# Wifi.net
KiCad netlist of a schematic drawn in Altium Designer
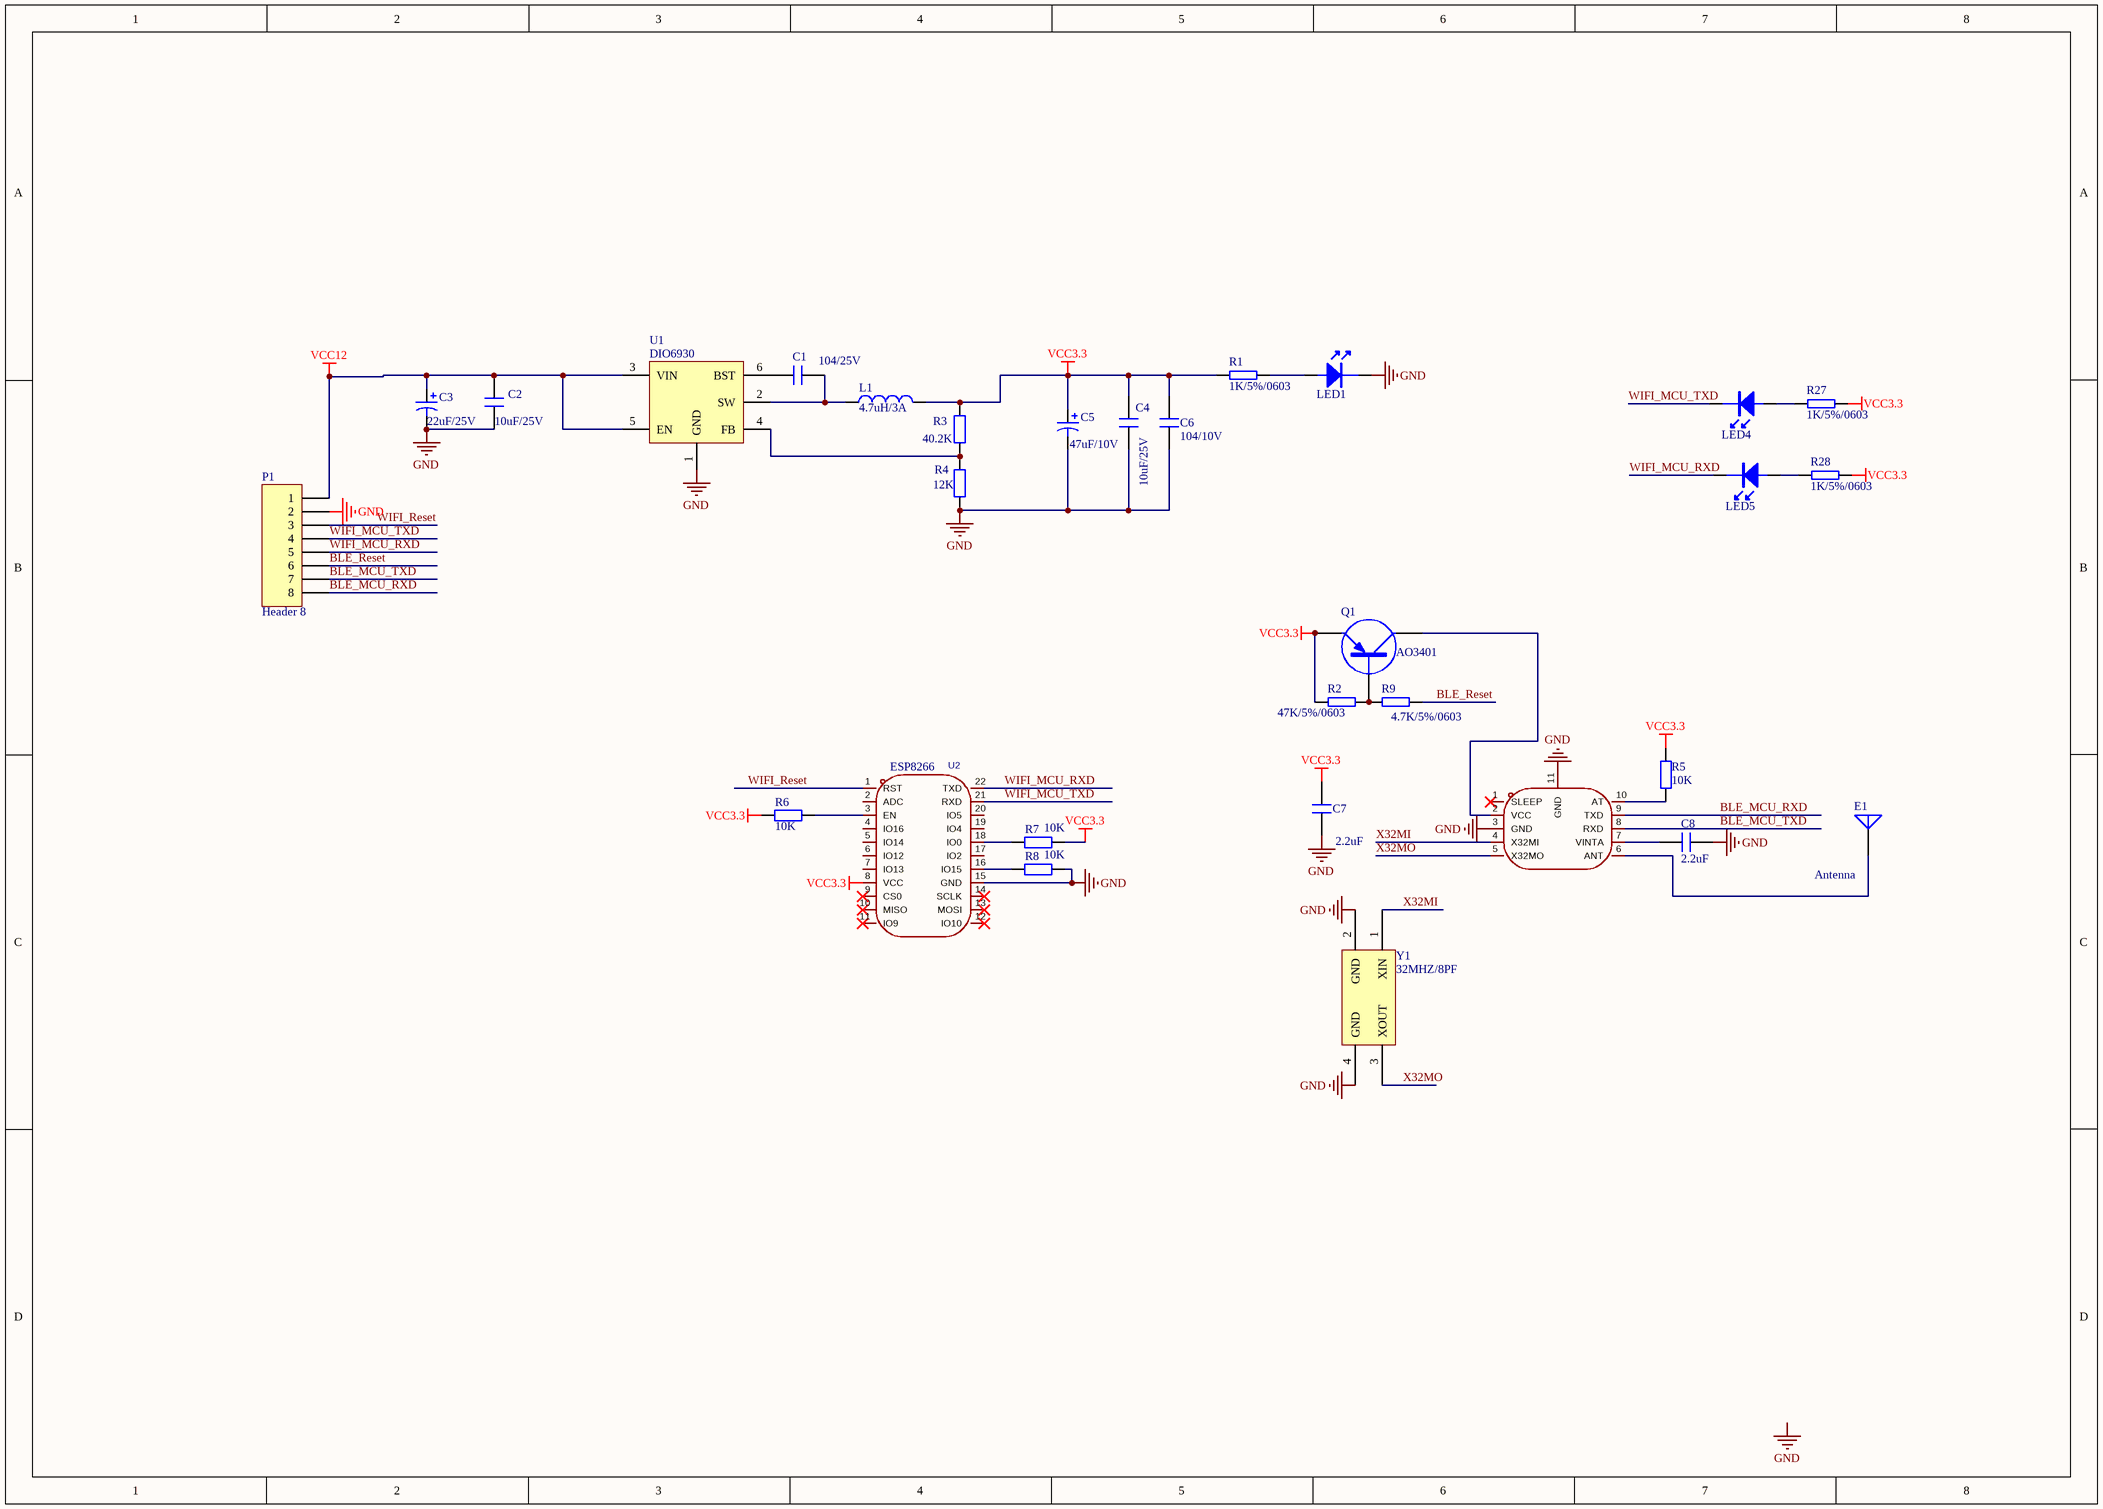
[diagram p0: Wifi.SchDoc]

(export (version "E")
  (design (tool "Eeschema 10.0.6"))
  (components
    (comp (ref "C1") (value "104/25V") (footprint "0603R") (libsource (lib "ES_Schematic") (part "CAP_1")))
    (comp (ref "C2") (value "10uF/25V") (footprint "0603R") (libsource (lib "ES_Schematic") (part "CAP")))
    (comp (ref "C3")
      (value "22uF/25V")
      (footprint "0805R")
      (description "Polarized Capacitor (Radial)")
      (fields (field (name "PUBLISHER") "Altium Limited"))
      (libsource (lib "Miscellaneous Devices") (part "Cap Pol1"))
    )
    (comp (ref "C4") (value "10uF/25V") (footprint "0603R") (libsource (lib "ES_Schematic") (part "CAP")))
    (comp (ref "C5")
      (value "47uF/10V")
      (footprint "0805R")
      (description "Polarized Capacitor (Radial)")
      (fields (field (name "PUBLISHER") "Altium Limited"))
      (libsource (lib "Miscellaneous Devices") (part "Cap Pol1"))
    )
    (comp (ref "C6") (value "104/10V") (footprint "0603R") (libsource (lib "ES_Schematic") (part "CAP_1")))
    (comp (ref "C7") (value "2.2uF") (footprint "0603R") (libsource (lib "ES_Schematic") (part "CAP_1")))
    (comp (ref "C8") (value "2.2uF") (footprint "0603R") (libsource (lib "ES_Schematic") (part "CAP_1")))
    (comp (ref "E1")
      (value "Antenna")
      (footprint "ANT-F-1-2.4G-1.6mmFR4-WCH")
      (description "Generic Antenna")
      (fields (field (name "PUBLISHER") "Altium Limited"))
      (libsource (lib "Miscellaneous Devices") (part "Antenna"))
    )
    (comp (ref "L1")
      (value "4.7uH/3A")
      (footprint "CD54")
      (description "Inductor")
      (fields (field (name "PUBLISHER") "Altium Limited"))
      (libsource (lib "Miscellaneous Devices") (part "Inductor"))
    )
    (comp (ref "LED1") (value "LED") (footprint "0603LED") (libsource (lib "ES_Schematic") (part "LED")))
    (comp (ref "LED4") (value "LED") (footprint "0603LED") (libsource (lib "ES_Schematic") (part "LED")))
    (comp (ref "LED5") (value "LED") (footprint "0603LED") (libsource (lib "ES_Schematic") (part "LED")))
    (comp (ref "P1")
      (value "Header 8")
      (footprint "HDR1X8")
      (description "Header, 8-Pin")
      (fields (field (name "PUBLISHER") "Altium Limited"))
      (libsource (lib "Miscellaneous Connectors") (part "Header 8"))
    )
    (comp (ref "Q1") (value "AO3401") (footprint "SOT-23") (libsource (lib "ES_Schematic") (part "PNP")))
    (comp (ref "R1") (value "1K/5%/0603") (footprint "0603R") (libsource (lib "ES_Schematic") (part "RES")))
    (comp (ref "R2") (value "47K/5%/0603") (footprint "0603R") (libsource (lib "ES_Schematic") (part "RES")))
    (comp (ref "R3")
      (value "40.2K")
      (footprint "0603R")
      (description "Resistor")
      (fields (field (name "PUBLISHER") "Altium Limited"))
      (libsource (lib "") (part "Res2_2"))
    )
    (comp (ref "R4")
      (value "12K")
      (footprint "0603R")
      (description "Resistor")
      (fields (field (name "PUBLISHER") "Altium Limited"))
      (libsource (lib "") (part "Res2_2"))
    )
    (comp (ref "R5")
      (value "10K")
      (footprint "0603R")
      (description "Resistor")
      (fields (field (name "PUBLISHER") "Altium Limited"))
      (libsource (lib "") (part "Res2_1"))
    )
    (comp (ref "R6")
      (value "10K")
      (footprint "0603R")
      (description "Resistor")
      (fields (field (name "PUBLISHER") "Altium Limited"))
      (libsource (lib "Miscellaneous Devices") (part "Res2"))
    )
    (comp (ref "R7")
      (value "10K")
      (footprint "0603R")
      (description "Resistor")
      (fields (field (name "PUBLISHER") "Altium Limited"))
      (libsource (lib "Miscellaneous Devices") (part "Res2"))
    )
    (comp (ref "R8")
      (value "10K")
      (footprint "0603R")
      (description "Resistor")
      (fields (field (name "PUBLISHER") "Altium Limited"))
      (libsource (lib "Miscellaneous Devices") (part "Res2"))
    )
    (comp (ref "R9") (value "4.7K/5%/0603") (footprint "0603R") (libsource (lib "ES_Schematic") (part "RES")))
    (comp (ref "R27") (value "1K/5%/0603") (footprint "0603R") (libsource (lib "ES_Schematic") (part "RES")))
    (comp (ref "R28") (value "1K/5%/0603") (footprint "0603R") (libsource (lib "ES_Schematic") (part "RES")))
    (comp (ref "U1")
      (value "DIO6930")
      (footprint "SOT-23-6DBV")
      (libsource (lib "ES_Schematic") (part "BL8032"))
    )
    (comp (ref "U2")
      (value "ESP8266")
      (footprint "ESP12E")
      (libsource (lib "altium-import") (part "root_0_ESP-12E_"))
    )
    (comp (ref "U3")
      (value "CH9141K")
      (footprint "CH9141K")
      (libsource (lib "altium-import") (part "root_0_CH9141K_"))
    )
    (comp (ref "Y1") (value "32MHZ/8PF") (footprint "3225") (libsource (lib "others") (part "12MHz无源")))
  )
  (nets
    (net (code "1") (name "/BLE_MCU_RXD") (class "Default")
      (node (ref "P1") (pin "8") (pinfunction "8_8") (pintype "passive"))
      (node (ref "U3") (pin "9") (pinfunction "TXD_9") (pintype "passive"))
    )
    (net (code "2") (name "/BLE_MCU_TXD") (class "Default")
      (node (ref "P1") (pin "7") (pinfunction "7_7") (pintype "passive"))
      (node (ref "U3") (pin "8") (pinfunction "RXD_8") (pintype "passive"))
    )
    (net (code "3") (name "/BLE_Reset") (class "Default")
      (node (ref "P1") (pin "6") (pinfunction "6_6") (pintype "passive"))
      (node (ref "R9") (pin "2") (pinfunction "2_2") (pintype "passive"))
    )
    (net (code "4") (name "/WIFI_MCU_RXD") (class "Default")
      (node (ref "LED5") (pin "2") (pinfunction "2_2") (pintype "passive"))
      (node (ref "P1") (pin "5") (pinfunction "5_5") (pintype "passive"))
      (node (ref "U2") (pin "22") (pinfunction "TXD_22") (pintype "passive"))
    )
    (net (code "5") (name "/WIFI_MCU_TXD") (class "Default")
      (node (ref "LED4") (pin "2") (pinfunction "2_2") (pintype "passive"))
      (node (ref "P1") (pin "4") (pinfunction "4_4") (pintype "passive"))
      (node (ref "U2") (pin "21") (pinfunction "RXD_21") (pintype "passive"))
    )
    (net (code "6") (name "/WIFI_Reset") (class "Default")
      (node (ref "P1") (pin "3") (pinfunction "3_3") (pintype "passive"))
      (node (ref "U2") (pin "1") (pinfunction "RST_1") (pintype "passive"))
    )
    (net (code "7") (name "/X32MI") (class "Default")
      (node (ref "U3") (pin "4") (pinfunction "X32MI_4") (pintype "passive"))
      (node (ref "Y1") (pin "1") (pinfunction "XIN_1") (pintype "passive"))
    )
    (net (code "8") (name "/X32MO") (class "Default")
      (node (ref "U3") (pin "5") (pinfunction "X32MO_5") (pintype "passive"))
      (node (ref "Y1") (pin "3") (pinfunction "XOUT_3") (pintype "passive"))
    )
    (net (code "9") (name "GND") (class "Default")
      (node (ref "C2") (pin "1") (pinfunction "1_1") (pintype "passive"))
      (node (ref "C3") (pin "2") (pinfunction "2_2") (pintype "passive"))
      (node (ref "C4") (pin "1") (pinfunction "1_1") (pintype "passive"))
      (node (ref "C5") (pin "2") (pinfunction "2_2") (pintype "passive"))
      (node (ref "C6") (pin "1") (pinfunction "1_1") (pintype "passive"))
      (node (ref "C7") (pin "1") (pinfunction "1_1") (pintype "passive"))
      (node (ref "C8") (pin "1") (pinfunction "1_1") (pintype "passive"))
      (node (ref "LED1") (pin "2") (pinfunction "2_2") (pintype "passive"))
      (node (ref "P1") (pin "2") (pinfunction "2_2") (pintype "passive"))
      (node (ref "R4") (pin "2") (pinfunction "2_2") (pintype "passive"))
      (node (ref "R8") (pin "2") (pinfunction "2_2") (pintype "passive"))
      (node (ref "U1") (pin "1") (pinfunction "GND_1") (pintype "passive"))
      (node (ref "U2") (pin "15") (pinfunction "GND_15") (pintype "passive"))
      (node (ref "U3") (pin "11") (pinfunction "GND_11") (pintype "passive"))
      (node (ref "U3") (pin "3") (pinfunction "GND_3") (pintype "passive"))
      (node (ref "Y1") (pin "2") (pinfunction "GND_2") (pintype "passive"))
      (node (ref "Y1") (pin "4") (pinfunction "GND_4") (pintype "passive"))
    )
    (net (code "10") (name "Net-(E1-A)") (class "Default")
      (node (ref "E1") (pin "1") (pinfunction "A_1") (pintype "passive"))
      (node (ref "U3") (pin "6") (pinfunction "ANT_6") (pintype "passive"))
    )
    (net (code "11") (name "Net-(LED1-Pad1)") (class "Default")
      (node (ref "LED1") (pin "1") (pinfunction "1_1") (pintype "passive"))
      (node (ref "R1") (pin "2") (pinfunction "2_2") (pintype "passive"))
    )
    (net (code "12") (name "Net-(LED4-Pad1)") (class "Default")
      (node (ref "LED4") (pin "1") (pinfunction "1_1") (pintype "passive"))
      (node (ref "R27") (pin "2") (pinfunction "2_2") (pintype "passive"))
    )
    (net (code "13") (name "Net-(LED5-Pad1)") (class "Default")
      (node (ref "LED5") (pin "1") (pinfunction "1_1") (pintype "passive"))
      (node (ref "R28") (pin "2") (pinfunction "2_2") (pintype "passive"))
    )
    (net (code "14") (name "Net-(Q1-B)") (class "Default")
      (node (ref "Q1") (pin "1") (pinfunction "B_1") (pintype "passive"))
      (node (ref "R2") (pin "1") (pinfunction "1_1") (pintype "passive"))
      (node (ref "R9") (pin "1") (pinfunction "1_1") (pintype "passive"))
    )
    (net (code "15") (name "Net-(Q1-C)") (class "Default")
      (node (ref "Q1") (pin "3") (pinfunction "C_3") (pintype "passive"))
      (node (ref "U3") (pin "2") (pinfunction "VCC_2") (pintype "passive"))
    )
    (net (code "16") (name "Net-(U1-BST)") (class "Default")
      (node (ref "C1") (pin "2") (pinfunction "2_2") (pintype "passive"))
      (node (ref "U1") (pin "6") (pinfunction "BST_6") (pintype "passive"))
    )
    (net (code "17") (name "Net-(U1-FB)") (class "Default")
      (node (ref "R3") (pin "2") (pinfunction "2_2") (pintype "passive"))
      (node (ref "R4") (pin "1") (pinfunction "1_1") (pintype "passive"))
      (node (ref "U1") (pin "4") (pinfunction "FB_4") (pintype "passive"))
    )
    (net (code "18") (name "Net-(U1-SW)") (class "Default")
      (node (ref "C1") (pin "1") (pinfunction "1_1") (pintype "passive"))
      (node (ref "L1") (pin "1") (pinfunction "1_1") (pintype "passive"))
      (node (ref "U1") (pin "2") (pinfunction "SW_2") (pintype "passive"))
    )
    (net (code "19") (name "Net-(U2-EN)") (class "Default")
      (node (ref "R6") (pin "2") (pinfunction "2_2") (pintype "passive"))
      (node (ref "U2") (pin "3") (pinfunction "EN_3") (pintype "passive"))
    )
    (net (code "20") (name "Net-(U2-IO0)") (class "Default")
      (node (ref "R7") (pin "1") (pinfunction "1_1") (pintype "passive"))
      (node (ref "U2") (pin "18") (pinfunction "IO0_18") (pintype "passive"))
    )
    (net (code "21") (name "Net-(U2-IO15)") (class "Default")
      (node (ref "R8") (pin "1") (pinfunction "1_1") (pintype "passive"))
      (node (ref "U2") (pin "16") (pinfunction "IO15_16") (pintype "passive"))
    )
    (net (code "22") (name "Net-(U3-AT)") (class "Default")
      (node (ref "R5") (pin "1") (pinfunction "1_1") (pintype "passive"))
      (node (ref "U3") (pin "10") (pinfunction "AT_10") (pintype "passive"))
    )
    (net (code "23") (name "Net-(U3-VINTA)") (class "Default")
      (node (ref "C8") (pin "2") (pinfunction "2_2") (pintype "passive"))
      (node (ref "U3") (pin "7") (pinfunction "VINTA_7") (pintype "passive"))
    )
    (net (code "24") (name "VCC3.3") (class "Default")
      (node (ref "C4") (pin "2") (pinfunction "2_2") (pintype "passive"))
      (node (ref "C5") (pin "1") (pinfunction "1_1") (pintype "passive"))
      (node (ref "C6") (pin "2") (pinfunction "2_2") (pintype "passive"))
      (node (ref "C7") (pin "2") (pinfunction "2_2") (pintype "passive"))
      (node (ref "L1") (pin "2") (pinfunction "2_2") (pintype "passive"))
      (node (ref "Q1") (pin "2") (pinfunction "E_2") (pintype "passive"))
      (node (ref "R1") (pin "1") (pinfunction "1_1") (pintype "passive"))
      (node (ref "R2") (pin "2") (pinfunction "2_2") (pintype "passive"))
      (node (ref "R27") (pin "1") (pinfunction "1_1") (pintype "passive"))
      (node (ref "R28") (pin "1") (pinfunction "1_1") (pintype "passive"))
      (node (ref "R3") (pin "1") (pinfunction "1_1") (pintype "passive"))
      (node (ref "R5") (pin "2") (pinfunction "2_2") (pintype "passive"))
      (node (ref "R6") (pin "1") (pinfunction "1_1") (pintype "passive"))
      (node (ref "R7") (pin "2") (pinfunction "2_2") (pintype "passive"))
      (node (ref "U2") (pin "8") (pinfunction "VCC_8") (pintype "passive"))
    )
    (net (code "25") (name "VCC12") (class "Default")
      (node (ref "C2") (pin "2") (pinfunction "2_2") (pintype "passive"))
      (node (ref "C3") (pin "1") (pinfunction "1_1") (pintype "passive"))
      (node (ref "P1") (pin "1") (pinfunction "1_1") (pintype "passive"))
      (node (ref "U1") (pin "3") (pinfunction "VIN_3") (pintype "passive"))
      (node (ref "U1") (pin "5") (pinfunction "EN_5") (pintype "passive"))
    )
    (net (code "26") (name "unconnected-(U2-ADC-Pad2)") (class "Default")
      (node (ref "U2") (pin "2") (pinfunction "ADC_2") (pintype "passive"))
    )
    (net (code "27") (name "unconnected-(U2-CS0-Pad9)") (class "Default")
      (node (ref "U2") (pin "9") (pinfunction "CS0_9") (pintype "passive+no_connect"))
    )
    (net (code "28") (name "unconnected-(U2-IO2-Pad17)") (class "Default")
      (node (ref "U2") (pin "17") (pinfunction "IO2_17") (pintype "passive"))
    )
    (net (code "29") (name "unconnected-(U2-IO4-Pad19)") (class "Default")
      (node (ref "U2") (pin "19") (pinfunction "IO4_19") (pintype "passive"))
    )
    (net (code "30") (name "unconnected-(U2-IO5-Pad20)") (class "Default")
      (node (ref "U2") (pin "20") (pinfunction "IO5_20") (pintype "passive"))
    )
    (net (code "31") (name "unconnected-(U2-IO9-Pad11)") (class "Default")
      (node (ref "U2") (pin "11") (pinfunction "IO9_11") (pintype "passive+no_connect"))
    )
    (net (code "32") (name "unconnected-(U2-IO10-Pad12)") (class "Default")
      (node (ref "U2") (pin "12") (pinfunction "IO10_12") (pintype "passive+no_connect"))
    )
    (net (code "33") (name "unconnected-(U2-IO12-Pad6)") (class "Default")
      (node (ref "U2") (pin "6") (pinfunction "IO12_6") (pintype "passive"))
    )
    (net (code "34") (name "unconnected-(U2-IO13-Pad7)") (class "Default")
      (node (ref "U2") (pin "7") (pinfunction "IO13_7") (pintype "passive"))
    )
    (net (code "35") (name "unconnected-(U2-IO14-Pad5)") (class "Default")
      (node (ref "U2") (pin "5") (pinfunction "IO14_5") (pintype "passive"))
    )
    (net (code "36") (name "unconnected-(U2-IO16-Pad4)") (class "Default")
      (node (ref "U2") (pin "4") (pinfunction "IO16_4") (pintype "passive"))
    )
    (net (code "37") (name "unconnected-(U2-MISO-Pad10)") (class "Default")
      (node (ref "U2") (pin "10") (pinfunction "MISO_10") (pintype "passive+no_connect"))
    )
    (net (code "38") (name "unconnected-(U2-MOSI-Pad13)") (class "Default")
      (node (ref "U2") (pin "13") (pinfunction "MOSI_13") (pintype "passive+no_connect"))
    )
    (net (code "39") (name "unconnected-(U2-SCLK-Pad14)") (class "Default")
      (node (ref "U2") (pin "14") (pinfunction "SCLK_14") (pintype "passive+no_connect"))
    )
    (net (code "40") (name "unconnected-(U3-SLEEP-Pad1)") (class "Default")
      (node (ref "U3") (pin "1") (pinfunction "SLEEP_1") (pintype "passive+no_connect"))
    )
  )
)
